# Sensor.net
KiCad netlist of a schematic drawn in Altium Designer
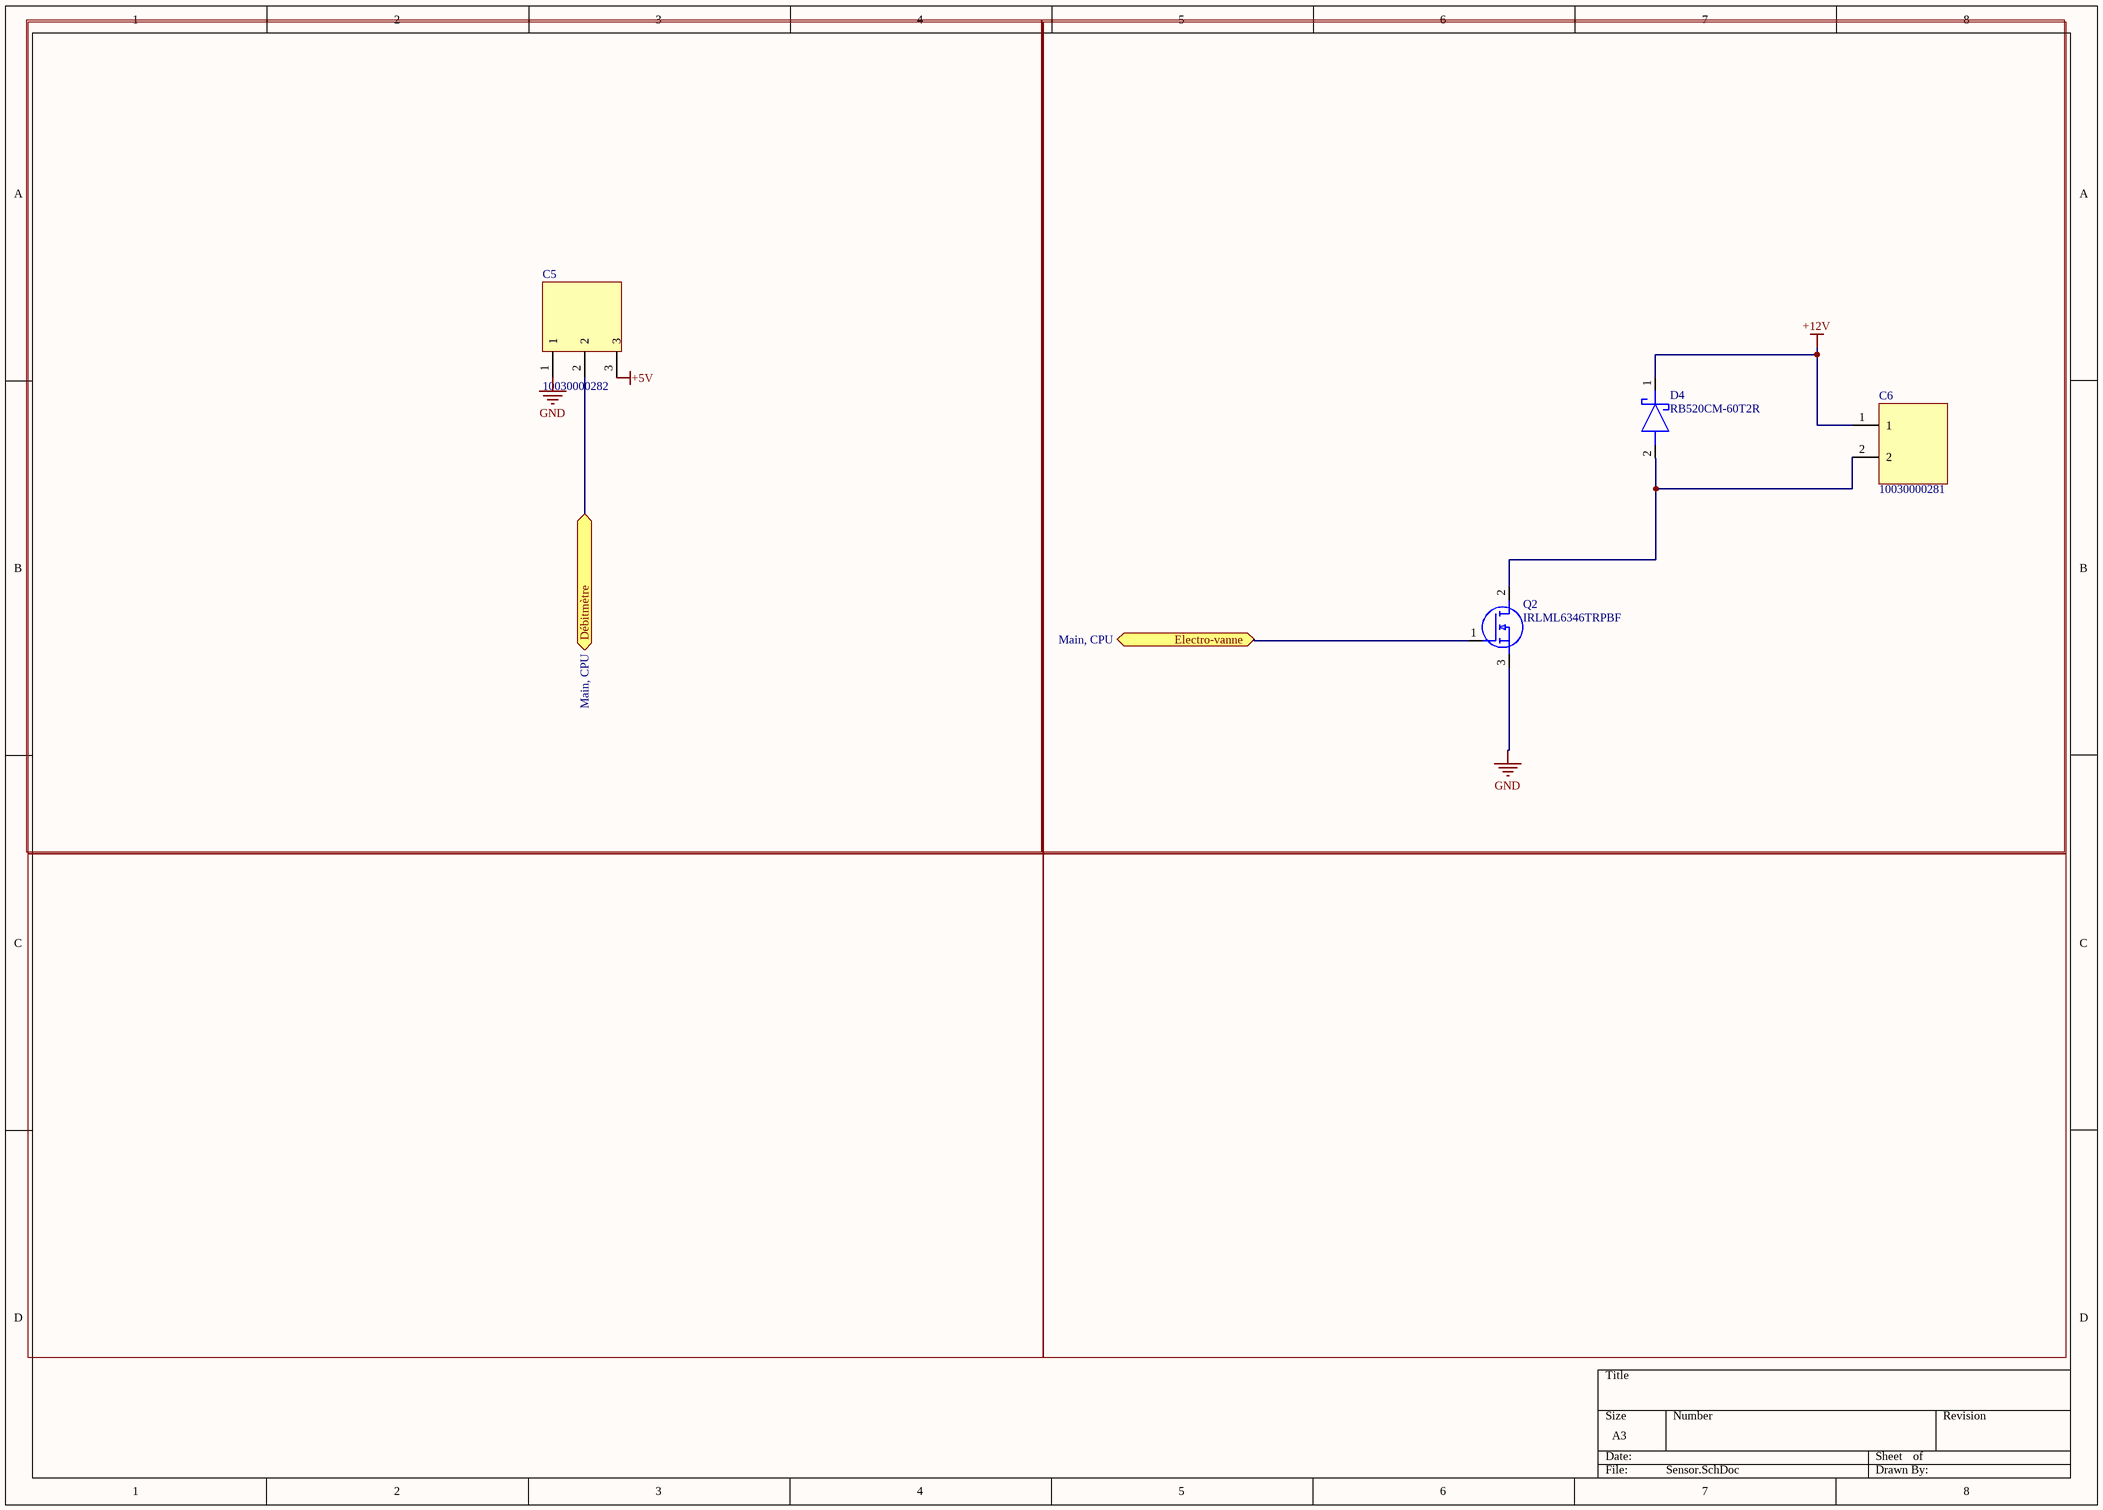
[diagram p0: Sensor.SchDoc]

(export (version "E")
  (design (tool "Eeschema 10.0.6"))
  (components
    (comp (ref "C5")
      (value "10030000282")
      (footprint "15EDGRC-5.08-03P-10030000282")
      (libsource (lib "SFMproject") (part "15EDGRC-5.08-03P"))
    )
    (comp (ref "C6")
      (value "10030000281")
      (footprint "5EDGRHC-7.62-02P-10020000939")
      (libsource (lib "SFMproject") (part "5EDGRHC-7.62-02P"))
    )
    (comp (ref "D4")
      (value "RB520CM-60T2R")
      (footprint "1SS400CSFHT2RA")
      (description "Schottky Diode")
      (fields (field (name "MOUSER PART NUMBER") "755-RB520CM-60T2R"))
      (libsource (lib "SFMproject") (part "RB520CM-60T2R"))
    )
    (comp (ref "Q2")
      (value "IRLML6346TRPBF")
      (footprint "SOT95P237X112-3N")
      (description "MOSFET MOSFT 3.4A 63mOhm 30V 2.5V drv capable")
      (fields
        (field (name "MOUSER PART NUMBER") "942-IRLML6346TRPBF")
        (field (name "MANUFACTURER_PART_NUMBER") "IRFR2905ZTRPBF")
      )
      (libsource (lib "SFMproject") (part "IRLML6346TRPBF"))
    )
  )
  (nets
    (net (code "1") (name "+5V") (class "Default")
      (node (ref "C5") (pin "3") (pinfunction "3_3") (pintype "passive"))
    )
    (net (code "2") (name "+12V") (class "Default")
      (node (ref "C6") (pin "1") (pinfunction "1_1") (pintype "passive"))
      (node (ref "D4") (pin "1") (pinfunction "K_1") (pintype "passive"))
    )
    (net (code "3") (name "/Débitmètre") (class "Default")
      (node (ref "C5") (pin "2") (pinfunction "2_2") (pintype "passive"))
    )
    (net (code "4") (name "/Electro-vanne") (class "Default")
      (node (ref "Q2") (pin "1") (pinfunction "G_1") (pintype "passive"))
    )
    (net (code "5") (name "GND") (class "Default")
      (node (ref "C5") (pin "1") (pinfunction "1_1") (pintype "passive"))
      (node (ref "Q2") (pin "3") (pinfunction "S_3") (pintype "passive"))
    )
    (net (code "6") (name "Net-(D4-A)") (class "Default")
      (node (ref "C6") (pin "2") (pinfunction "2_2") (pintype "passive"))
      (node (ref "D4") (pin "2") (pinfunction "A_2") (pintype "passive"))
      (node (ref "Q2") (pin "2") (pinfunction "D_2") (pintype "passive"))
    )
  )
)
